# nRF52810_Beacon.net
KiCad netlist of a schematic drawn in EAGLE
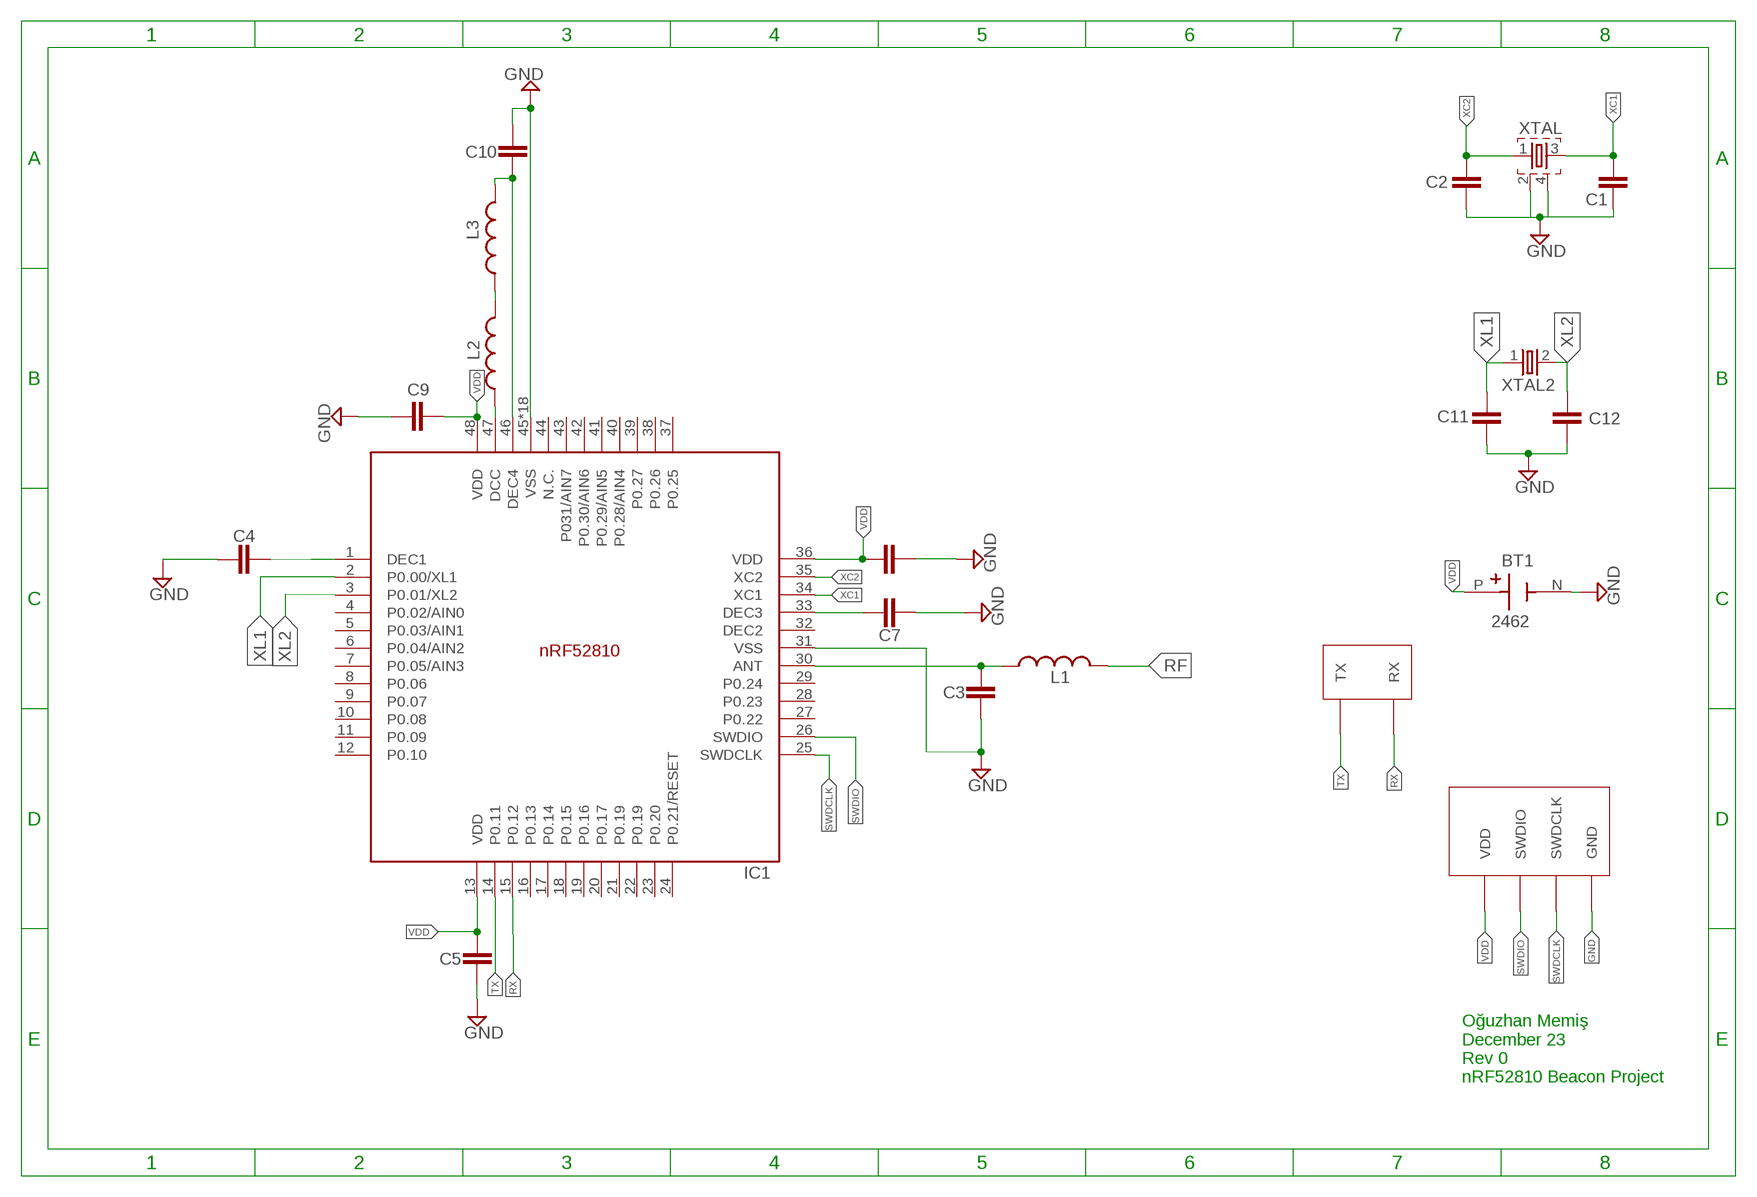
[diagram p0: schematic, sheet 1]

(export (version "E")
  (design (tool "Eeschema 10.0.6"))
  (components
    (comp (ref "BT1")
      (value "2462")
      (footprint "eagle-import:BAT_2462")
      (fields (field (name "MF") "Keystone"))
      (libsource (lib "eagle-import") (part "2462"))
    )
    (comp (ref "C1")
      (value "12pF")
      (footprint "eagle-import:RESC0402_N")
      (libsource (lib "eagle-import") (part "CAPACITOR_0402_N"))
    )
    (comp (ref "C2")
      (value "12pF")
      (footprint "eagle-import:RESC0402_N")
      (libsource (lib "eagle-import") (part "CAPACITOR_0402_N"))
    )
    (comp (ref "C3")
      (value "0.8pF")
      (footprint "eagle-import:RESC0402_N")
      (libsource (lib "eagle-import") (part "CAPACITOR_0402_N"))
    )
    (comp (ref "C4")
      (value "100nF")
      (footprint "eagle-import:RESC0402_N")
      (libsource (lib "eagle-import") (part "CAPACITOR_0402_N"))
    )
    (comp (ref "C5")
      (value "100nF")
      (footprint "eagle-import:RESC0402_N")
      (libsource (lib "eagle-import") (part "CAPACITOR_0402_N"))
    )
    (comp (ref "C7")
      (value "100pF")
      (footprint "eagle-import:RESC0402_N")
      (libsource (lib "eagle-import") (part "CAPACITOR_0402_N"))
    )
    (comp (ref "C8")
      (value "100nF")
      (footprint "eagle-import:RESC0402_N")
      (libsource (lib "eagle-import") (part "CAPACITOR_0402_N"))
    )
    (comp (ref "C9")
      (value "4.7uF")
      (footprint "eagle-import:RESC0603_N")
      (libsource (lib "eagle-import") (part "CAPACITOR_0603_N"))
    )
    (comp (ref "C10")
      (value "1uF")
      (footprint "eagle-import:RESC0603_N")
      (libsource (lib "eagle-import") (part "CAPACITOR_0603_N"))
    )
    (comp (ref "C11")
      (value "12pF")
      (footprint "eagle-import:RESC0402_N")
      (libsource (lib "eagle-import") (part "CAPACITOR_0402_N"))
    )
    (comp (ref "C12")
      (value "12pF")
      (footprint "eagle-import:RESC0402_N")
      (libsource (lib "eagle-import") (part "CAPACITOR_0402_N"))
    )
    (comp (ref "IC1")
      (value "NRF52810_QF48")
      (footprint "eagle-import:QFN40P600X600X90-48_N")
      (libsource (lib "eagle-import") (part "NRF52810_QF48"))
    )
    (comp (ref "L1")
      (value "3.9nF")
      (footprint "eagle-import:RESC0402_N")
      (libsource (lib "eagle-import") (part "INDUCTOR_0402_N"))
    )
    (comp (ref "L2")
      (value "10uH")
      (footprint "eagle-import:RESC0402_N")
      (libsource (lib "eagle-import") (part "INDUCTOR_0402_N"))
    )
    (comp (ref "L3")
      (value "15nH")
      (footprint "eagle-import:RESC0402_N")
      (libsource (lib "eagle-import") (part "INDUCTOR_0402_N"))
    )
    (comp (ref "U$1")
      (value "SWD")
      (footprint "eagle-import:SWD")
      (libsource (lib "eagle-import") (part "SWD"))
    )
    (comp (ref "U$2")
      (value "UART")
      (footprint "eagle-import:UART")
      (libsource (lib "eagle-import") (part "UART"))
    )
    (comp (ref "XTAL")
      (value "32MHz SMD2016")
      (footprint "eagle-import:BT-XTAL_2016_N")
      (libsource (lib "eagle-import") (part "XTAL_32MHZ"))
    )
    (comp (ref "XTAL2")
      (value "32KHz")
      (footprint "eagle-import:XTAL_3215_N")
      (libsource (lib "eagle-import") (part "XTAL_32KHZ"))
    )
  )
  (nets
    (net (code "1") (name "GND") (class "Default")
      (node (ref "BT1") (pin "N") (pinfunction "NEG_N") (pintype "passive"))
      (node (ref "C1") (pin "1") (pinfunction "1_1") (pintype "passive"))
      (node (ref "C10") (pin "2") (pinfunction "2_2") (pintype "passive"))
      (node (ref "C11") (pin "1") (pinfunction "1_1") (pintype "passive"))
      (node (ref "C12") (pin "1") (pinfunction "1_1") (pintype "passive"))
      (node (ref "C2") (pin "1") (pinfunction "1_1") (pintype "passive"))
      (node (ref "C3") (pin "2") (pinfunction "2_2") (pintype "passive"))
      (node (ref "C4") (pin "1") (pinfunction "1_1") (pintype "passive"))
      (node (ref "C5") (pin "2") (pinfunction "2_2") (pintype "passive"))
      (node (ref "C7") (pin "2") (pinfunction "2_2") (pintype "passive"))
      (node (ref "C8") (pin "2") (pinfunction "2_2") (pintype "passive"))
      (node (ref "C9") (pin "1") (pinfunction "1_1") (pintype "passive"))
      (node (ref "IC1") (pin "31") (pinfunction "VSS_31") (pintype "bidirectional"))
      (node (ref "IC1") (pin "45") (pinfunction "VSS_45") (pintype "bidirectional"))
      (node (ref "IC1") (pin "PAD") (pinfunction "VSS_PAD") (pintype "bidirectional"))
      (node (ref "IC1") (pin "PAD@VIA01") (pinfunction "VSS_PAD@VIA01") (pintype "bidirectional"))
      (node (ref "IC1") (pin "PAD@VIA02") (pinfunction "VSS_PAD@VIA02") (pintype "bidirectional"))
      (node (ref "IC1") (pin "PAD@VIA03") (pinfunction "VSS_PAD@VIA03") (pintype "bidirectional"))
      (node (ref "IC1") (pin "PAD@VIA04") (pinfunction "VSS_PAD@VIA04") (pintype "bidirectional"))
      (node (ref "IC1") (pin "PAD@VIA05") (pinfunction "VSS_PAD@VIA05") (pintype "bidirectional"))
      (node (ref "IC1") (pin "PAD@VIA06") (pinfunction "VSS_PAD@VIA06") (pintype "bidirectional"))
      (node (ref "IC1") (pin "PAD@VIA07") (pinfunction "VSS_PAD@VIA07") (pintype "bidirectional"))
      (node (ref "IC1") (pin "PAD@VIA08") (pinfunction "VSS_PAD@VIA08") (pintype "bidirectional"))
      (node (ref "IC1") (pin "PAD@VIA09") (pinfunction "VSS_PAD@VIA09") (pintype "bidirectional"))
      (node (ref "IC1") (pin "PAD@VIA10") (pinfunction "VSS_PAD@VIA10") (pintype "bidirectional"))
      (node (ref "IC1") (pin "PAD@VIA11") (pinfunction "VSS_PAD@VIA11") (pintype "bidirectional"))
      (node (ref "IC1") (pin "PAD@VIA12") (pinfunction "VSS_PAD@VIA12") (pintype "bidirectional"))
      (node (ref "IC1") (pin "PAD@VIA13") (pinfunction "VSS_PAD@VIA13") (pintype "bidirectional"))
      (node (ref "IC1") (pin "PAD@VIA14") (pinfunction "VSS_PAD@VIA14") (pintype "bidirectional"))
      (node (ref "IC1") (pin "PAD@VIA15") (pinfunction "VSS_PAD@VIA15") (pintype "bidirectional"))
      (node (ref "IC1") (pin "PAD@VIA16") (pinfunction "VSS_PAD@VIA16") (pintype "bidirectional"))
      (node (ref "U$1") (pin "GND") (pinfunction "GND_GND") (pintype "bidirectional"))
      (node (ref "XTAL") (pin "2") (pinfunction "2_2") (pintype "passive"))
      (node (ref "XTAL") (pin "4") (pinfunction "4_4") (pintype "passive"))
    )
    (net (code "2") (name "Net-(IC1-ANT)") (class "Default")
      (node (ref "C3") (pin "1") (pinfunction "1_1") (pintype "passive"))
      (node (ref "IC1") (pin "30") (pinfunction "ANT_30") (pintype "bidirectional"))
      (node (ref "L1") (pin "1") (pinfunction "1_1") (pintype "passive"))
    )
    (net (code "3") (name "Net-(IC1-DCC)") (class "Default")
      (node (ref "IC1") (pin "47") (pinfunction "DCC_47") (pintype "bidirectional"))
      (node (ref "L2") (pin "1") (pinfunction "1_1") (pintype "passive"))
    )
    (net (code "4") (name "Net-(IC1-DEC1)") (class "Default")
      (node (ref "C4") (pin "2") (pinfunction "2_2") (pintype "passive"))
      (node (ref "IC1") (pin "1") (pinfunction "DEC1_1") (pintype "bidirectional"))
    )
    (net (code "5") (name "Net-(IC1-DEC3)") (class "Default")
      (node (ref "C7") (pin "1") (pinfunction "1_1") (pintype "passive"))
      (node (ref "IC1") (pin "33") (pinfunction "DEC3_33") (pintype "bidirectional"))
    )
    (net (code "6") (name "Net-(IC1-DEC4)") (class "Default")
      (node (ref "C10") (pin "1") (pinfunction "1_1") (pintype "passive"))
      (node (ref "IC1") (pin "46") (pinfunction "DEC4_46") (pintype "bidirectional"))
      (node (ref "L3") (pin "2") (pinfunction "2_2") (pintype "passive"))
    )
    (net (code "7") (name "Net-(L2-Pad2)") (class "Default")
      (node (ref "L2") (pin "2") (pinfunction "2_2") (pintype "passive"))
      (node (ref "L3") (pin "1") (pinfunction "1_1") (pintype "passive"))
    )
    (net (code "8") (name "RF") (class "Default")
      (node (ref "L1") (pin "2") (pinfunction "2_2") (pintype "passive"))
    )
    (net (code "9") (name "RX") (class "Default")
      (node (ref "IC1") (pin "15") (pinfunction "P0.12_15") (pintype "bidirectional"))
      (node (ref "U$2") (pin "RX") (pinfunction "RX_RX") (pintype "bidirectional"))
    )
    (net (code "10") (name "SWDCLK") (class "Default")
      (node (ref "IC1") (pin "25") (pinfunction "SWDCLK_25") (pintype "bidirectional"))
      (node (ref "U$1") (pin "SWDCLK") (pinfunction "SWDCLK_SWDCLK") (pintype "bidirectional"))
    )
    (net (code "11") (name "SWDIO") (class "Default")
      (node (ref "IC1") (pin "26") (pinfunction "SWDIO_26") (pintype "bidirectional"))
      (node (ref "U$1") (pin "SWDIO") (pinfunction "SWDIO_SWDIO") (pintype "bidirectional"))
    )
    (net (code "12") (name "TX") (class "Default")
      (node (ref "IC1") (pin "14") (pinfunction "P0.11_14") (pintype "bidirectional"))
      (node (ref "U$2") (pin "TX") (pinfunction "TX_TX") (pintype "bidirectional"))
    )
    (net (code "13") (name "VDD") (class "Default")
      (node (ref "BT1") (pin "P") (pinfunction "POS_P") (pintype "passive"))
      (node (ref "C5") (pin "1") (pinfunction "1_1") (pintype "passive"))
      (node (ref "C8") (pin "1") (pinfunction "1_1") (pintype "passive"))
      (node (ref "C9") (pin "2") (pinfunction "2_2") (pintype "passive"))
      (node (ref "IC1") (pin "13") (pinfunction "VDD_13") (pintype "bidirectional"))
      (node (ref "IC1") (pin "36") (pinfunction "VDD_36") (pintype "bidirectional"))
      (node (ref "IC1") (pin "48") (pinfunction "VDD_48") (pintype "bidirectional"))
      (node (ref "U$1") (pin "VDD") (pinfunction "VDD_VDD") (pintype "bidirectional"))
    )
    (net (code "14") (name "XC1") (class "Default")
      (node (ref "C1") (pin "2") (pinfunction "2_2") (pintype "passive"))
      (node (ref "IC1") (pin "34") (pinfunction "XC1_34") (pintype "bidirectional"))
      (node (ref "XTAL") (pin "3") (pinfunction "3_3") (pintype "passive"))
    )
    (net (code "15") (name "XC2") (class "Default")
      (node (ref "C2") (pin "2") (pinfunction "2_2") (pintype "passive"))
      (node (ref "IC1") (pin "35") (pinfunction "XC2_35") (pintype "bidirectional"))
      (node (ref "XTAL") (pin "1") (pinfunction "1_1") (pintype "passive"))
    )
    (net (code "16") (name "XL1") (class "Default")
      (node (ref "C11") (pin "2") (pinfunction "2_2") (pintype "passive"))
      (node (ref "IC1") (pin "2") (pinfunction "P0.00/XL1_2") (pintype "bidirectional"))
      (node (ref "XTAL2") (pin "1") (pinfunction "1_1") (pintype "passive"))
    )
    (net (code "17") (name "XL2") (class "Default")
      (node (ref "C12") (pin "2") (pinfunction "2_2") (pintype "passive"))
      (node (ref "IC1") (pin "3") (pinfunction "P0.01/XL2_3") (pintype "bidirectional"))
      (node (ref "XTAL2") (pin "2") (pinfunction "2_2") (pintype "passive"))
    )
    (net (code "18") (name "unconnected-(IC1-DEC2-Pad32)") (class "Default")
      (node (ref "IC1") (pin "32") (pinfunction "DEC2_32") (pintype "bidirectional"))
    )
    (net (code "19") (name "unconnected-(IC1-N.C.-Pad44)") (class "Default")
      (node (ref "IC1") (pin "44") (pinfunction "N.C._44") (pintype "bidirectional"))
    )
    (net (code "20") (name "unconnected-(IC1-P0.02{slash}AIN0-Pad4)") (class "Default")
      (node (ref "IC1") (pin "4") (pinfunction "P0.02/AIN0_4") (pintype "bidirectional"))
    )
    (net (code "21") (name "unconnected-(IC1-P0.03{slash}AIN1-Pad5)") (class "Default")
      (node (ref "IC1") (pin "5") (pinfunction "P0.03/AIN1_5") (pintype "bidirectional"))
    )
    (net (code "22") (name "unconnected-(IC1-P0.04{slash}AIN2-Pad6)") (class "Default")
      (node (ref "IC1") (pin "6") (pinfunction "P0.04/AIN2_6") (pintype "bidirectional"))
    )
    (net (code "23") (name "unconnected-(IC1-P0.05{slash}AIN3-Pad7)") (class "Default")
      (node (ref "IC1") (pin "7") (pinfunction "P0.05/AIN3_7") (pintype "bidirectional"))
    )
    (net (code "24") (name "unconnected-(IC1-P0.06-Pad8)") (class "Default")
      (node (ref "IC1") (pin "8") (pinfunction "P0.06_8") (pintype "bidirectional"))
    )
    (net (code "25") (name "unconnected-(IC1-P0.07-Pad9)") (class "Default")
      (node (ref "IC1") (pin "9") (pinfunction "P0.07_9") (pintype "bidirectional"))
    )
    (net (code "26") (name "unconnected-(IC1-P0.08-Pad10)") (class "Default")
      (node (ref "IC1") (pin "10") (pinfunction "P0.08_10") (pintype "bidirectional"))
    )
    (net (code "27") (name "unconnected-(IC1-P0.09-Pad11)") (class "Default")
      (node (ref "IC1") (pin "11") (pinfunction "P0.09_11") (pintype "bidirectional"))
    )
    (net (code "28") (name "unconnected-(IC1-P0.10-Pad12)") (class "Default")
      (node (ref "IC1") (pin "12") (pinfunction "P0.10_12") (pintype "bidirectional"))
    )
    (net (code "29") (name "unconnected-(IC1-P0.13-Pad16)") (class "Default")
      (node (ref "IC1") (pin "16") (pinfunction "P0.13_16") (pintype "bidirectional"))
    )
    (net (code "30") (name "unconnected-(IC1-P0.14-Pad17)") (class "Default")
      (node (ref "IC1") (pin "17") (pinfunction "P0.14_17") (pintype "bidirectional"))
    )
    (net (code "31") (name "unconnected-(IC1-P0.15-Pad18)") (class "Default")
      (node (ref "IC1") (pin "18") (pinfunction "P0.15_18") (pintype "bidirectional"))
    )
    (net (code "32") (name "unconnected-(IC1-P0.16-Pad19)") (class "Default")
      (node (ref "IC1") (pin "19") (pinfunction "P0.16_19") (pintype "bidirectional"))
    )
    (net (code "33") (name "unconnected-(IC1-P0.17-Pad20)") (class "Default")
      (node (ref "IC1") (pin "20") (pinfunction "P0.17_20") (pintype "bidirectional"))
    )
    (net (code "34") (name "unconnected-(IC1-P0.19-Pad21)") (class "Default")
      (node (ref "IC1") (pin "21") (pinfunction "P0.19_21") (pintype "bidirectional"))
    )
    (net (code "35") (name "unconnected-(IC1-P0.19-Pad22)") (class "Default")
      (node (ref "IC1") (pin "22") (pinfunction "P0.19_22") (pintype "bidirectional"))
    )
    (net (code "36") (name "unconnected-(IC1-P0.20-Pad23)") (class "Default")
      (node (ref "IC1") (pin "23") (pinfunction "P0.20_23") (pintype "bidirectional"))
    )
    (net (code "37") (name "unconnected-(IC1-P0.21{slash}RESET-Pad24)") (class "Default")
      (node (ref "IC1") (pin "24") (pinfunction "P0.21/RESET_24") (pintype "bidirectional"))
    )
    (net (code "38") (name "unconnected-(IC1-P0.22-Pad27)") (class "Default")
      (node (ref "IC1") (pin "27") (pinfunction "P0.22_27") (pintype "bidirectional"))
    )
    (net (code "39") (name "unconnected-(IC1-P0.23-Pad28)") (class "Default")
      (node (ref "IC1") (pin "28") (pinfunction "P0.23_28") (pintype "bidirectional"))
    )
    (net (code "40") (name "unconnected-(IC1-P0.24-Pad29)") (class "Default")
      (node (ref "IC1") (pin "29") (pinfunction "P0.24_29") (pintype "bidirectional"))
    )
    (net (code "41") (name "unconnected-(IC1-P0.25-Pad37)") (class "Default")
      (node (ref "IC1") (pin "37") (pinfunction "P0.25_37") (pintype "bidirectional"))
    )
    (net (code "42") (name "unconnected-(IC1-P0.26-Pad38)") (class "Default")
      (node (ref "IC1") (pin "38") (pinfunction "P0.26_38") (pintype "bidirectional"))
    )
    (net (code "43") (name "unconnected-(IC1-P0.27-Pad39)") (class "Default")
      (node (ref "IC1") (pin "39") (pinfunction "P0.27_39") (pintype "bidirectional"))
    )
    (net (code "44") (name "unconnected-(IC1-P0.28{slash}AIN4-Pad40)") (class "Default")
      (node (ref "IC1") (pin "40") (pinfunction "P0.28/AIN4_40") (pintype "bidirectional"))
    )
    (net (code "45") (name "unconnected-(IC1-P0.29{slash}AIN5-Pad41)") (class "Default")
      (node (ref "IC1") (pin "41") (pinfunction "P0.29/AIN5_41") (pintype "bidirectional"))
    )
    (net (code "46") (name "unconnected-(IC1-P0.30{slash}AIN6-Pad42)") (class "Default")
      (node (ref "IC1") (pin "42") (pinfunction "P0.30/AIN6_42") (pintype "bidirectional"))
    )
    (net (code "47") (name "unconnected-(IC1-P031{slash}AIN7-Pad43)") (class "Default")
      (node (ref "IC1") (pin "43") (pinfunction "P031/AIN7_43") (pintype "bidirectional"))
    )
  )
)
